# 1X_4LED.net
KiCad netlist of a schematic drawn in Altium Designer
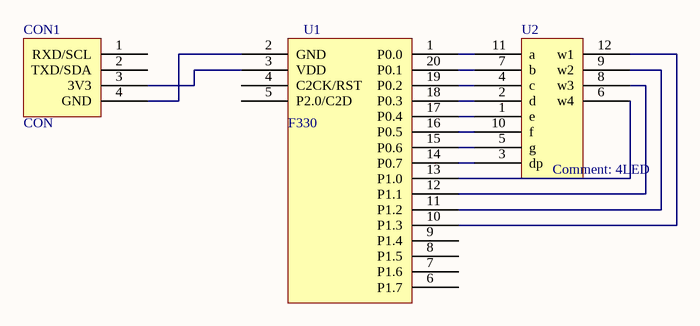
[diagram p0: 1X 4LED.SCHDOC]

(export (version "E")
  (design (tool "Eeschema 10.0.6"))
  (components
    (comp (ref "CON1") (value "CON") (footprint "PH-SIDE") (libsource (lib "*") (part "CON")))
    (comp (ref "U1") (value "F330") (footprint "QFN20") (libsource (lib "*") (part "F330")))
    (comp (ref "U2") (value "4LED") (footprint "4LED") (libsource (lib "*") (part "4LED")))
  )
  (nets
    (net (code "1") (name "Net-(CON1-3V3)") (class "Default")
      (node (ref "CON1") (pin "3") (pinfunction "3V3_3") (pintype "passive"))
      (node (ref "U1") (pin "3") (pinfunction "VDD_3") (pintype "passive"))
    )
    (net (code "2") (name "Net-(CON1-GND)") (class "Default")
      (node (ref "CON1") (pin "4") (pinfunction "GND_4") (pintype "passive"))
      (node (ref "U1") (pin "2") (pinfunction "GND_2") (pintype "passive"))
    )
    (net (code "3") (name "Net-(U1-P0.0)") (class "Default")
      (node (ref "U1") (pin "1") (pinfunction "P0.0_1") (pintype "passive"))
      (node (ref "U2") (pin "11") (pinfunction "a_11") (pintype "passive"))
    )
    (net (code "4") (name "Net-(U1-P0.1)") (class "Default")
      (node (ref "U1") (pin "20") (pinfunction "P0.1_20") (pintype "passive"))
      (node (ref "U2") (pin "7") (pinfunction "b_7") (pintype "passive"))
    )
    (net (code "5") (name "Net-(U1-P0.2)") (class "Default")
      (node (ref "U1") (pin "19") (pinfunction "P0.2_19") (pintype "passive"))
      (node (ref "U2") (pin "4") (pinfunction "c_4") (pintype "passive"))
    )
    (net (code "6") (name "Net-(U1-P0.3)") (class "Default")
      (node (ref "U1") (pin "18") (pinfunction "P0.3_18") (pintype "passive"))
      (node (ref "U2") (pin "2") (pinfunction "d_2") (pintype "passive"))
    )
    (net (code "7") (name "Net-(U1-P0.4)") (class "Default")
      (node (ref "U1") (pin "17") (pinfunction "P0.4_17") (pintype "passive"))
      (node (ref "U2") (pin "1") (pinfunction "e_1") (pintype "passive"))
    )
    (net (code "8") (name "Net-(U1-P0.5)") (class "Default")
      (node (ref "U1") (pin "16") (pinfunction "P0.5_16") (pintype "passive"))
      (node (ref "U2") (pin "10") (pinfunction "f_10") (pintype "passive"))
    )
    (net (code "9") (name "Net-(U1-P0.6)") (class "Default")
      (node (ref "U1") (pin "15") (pinfunction "P0.6_15") (pintype "passive"))
      (node (ref "U2") (pin "5") (pinfunction "g_5") (pintype "passive"))
    )
    (net (code "10") (name "Net-(U1-P0.7)") (class "Default")
      (node (ref "U1") (pin "14") (pinfunction "P0.7_14") (pintype "passive"))
      (node (ref "U2") (pin "3") (pinfunction "dp_3") (pintype "passive"))
    )
    (net (code "11") (name "Net-(U1-P1.0)") (class "Default")
      (node (ref "U1") (pin "13") (pinfunction "P1.0_13") (pintype "passive"))
      (node (ref "U2") (pin "6") (pinfunction "w4_6") (pintype "passive"))
    )
    (net (code "12") (name "Net-(U1-P1.1)") (class "Default")
      (node (ref "U1") (pin "12") (pinfunction "P1.1_12") (pintype "passive"))
      (node (ref "U2") (pin "8") (pinfunction "w3_8") (pintype "passive"))
    )
    (net (code "13") (name "Net-(U1-P1.2)") (class "Default")
      (node (ref "U1") (pin "11") (pinfunction "P1.2_11") (pintype "passive"))
      (node (ref "U2") (pin "9") (pinfunction "w2_9") (pintype "passive"))
    )
    (net (code "14") (name "Net-(U1-P1.3)") (class "Default")
      (node (ref "U1") (pin "10") (pinfunction "P1.3_10") (pintype "passive"))
      (node (ref "U2") (pin "12") (pinfunction "w1_12") (pintype "passive"))
    )
    (net (code "15") (name "unconnected-(CON1-RXD{slash}SCL-Pad1)") (class "Default")
      (node (ref "CON1") (pin "1") (pinfunction "RXD/SCL_1") (pintype "passive"))
    )
    (net (code "16") (name "unconnected-(CON1-TXD{slash}SDA-Pad2)") (class "Default")
      (node (ref "CON1") (pin "2") (pinfunction "TXD/SDA_2") (pintype "passive"))
    )
    (net (code "17") (name "unconnected-(U1-C2CK{slash}RST-Pad4)") (class "Default")
      (node (ref "U1") (pin "4") (pinfunction "C2CK/RST_4") (pintype "passive"))
    )
    (net (code "18") (name "unconnected-(U1-P1.4-Pad9)") (class "Default")
      (node (ref "U1") (pin "9") (pinfunction "P1.4_9") (pintype "passive"))
    )
    (net (code "19") (name "unconnected-(U1-P1.5-Pad8)") (class "Default")
      (node (ref "U1") (pin "8") (pinfunction "P1.5_8") (pintype "passive"))
    )
    (net (code "20") (name "unconnected-(U1-P1.6-Pad7)") (class "Default")
      (node (ref "U1") (pin "7") (pinfunction "P1.6_7") (pintype "passive"))
    )
    (net (code "21") (name "unconnected-(U1-P1.7-Pad6)") (class "Default")
      (node (ref "U1") (pin "6") (pinfunction "P1.7_6") (pintype "passive"))
    )
    (net (code "22") (name "unconnected-(U1-P2.0{slash}C2D-Pad5)") (class "Default")
      (node (ref "U1") (pin "5") (pinfunction "P2.0/C2D_5") (pintype "passive"))
    )
  )
)
